# tweakfuzz.net
KiCad netlist of a schematic drawn in EAGLE
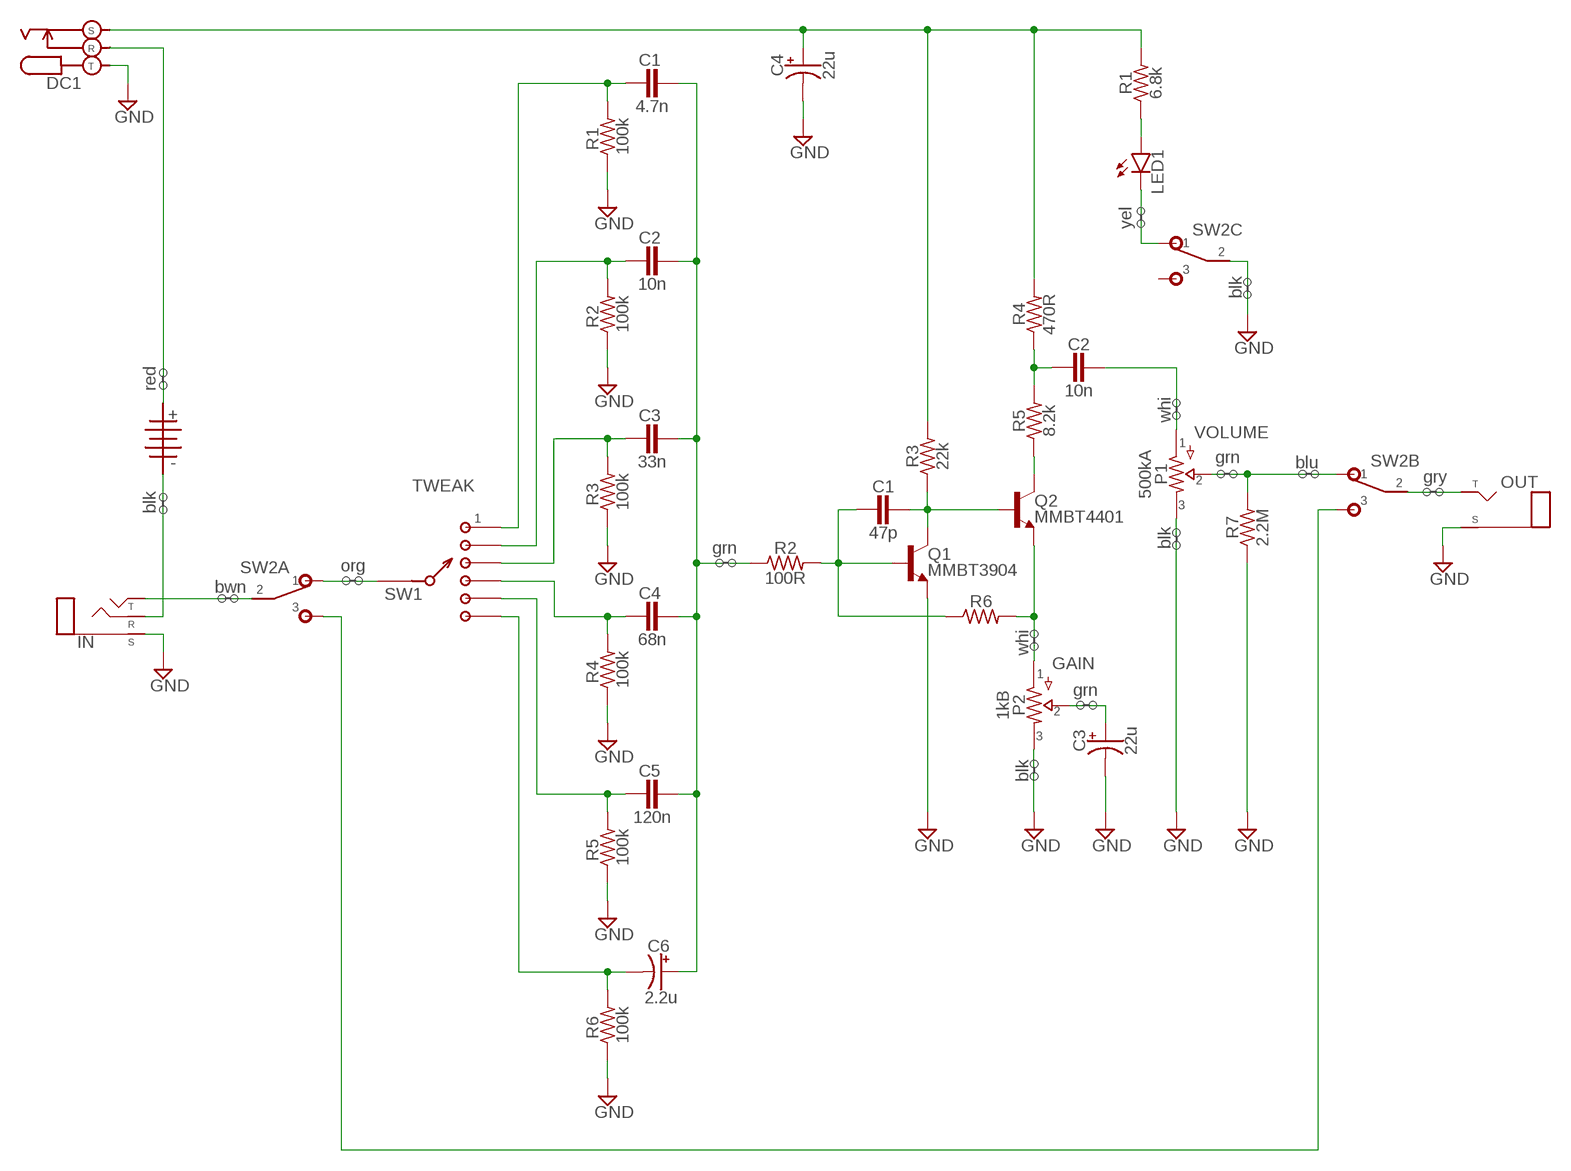
[diagram p0: schematic, sheet 1]

(export (version "E")
  (design (tool "Eeschema 10.0.6"))
  (components
    (comp (ref "1")
      (value "BATTERY")
      (footprint "eagle-import:TWO_PADS")
      (libsource (lib "eagle-import") (part "BATTERY"))
    )
    (comp (ref "C1")
      (value "47p")
      (footprint "eagle-import:BOX_SMALL")
      (libsource (lib "eagle-import") (part "CER/FILMBOX.1"))
    )
    (comp (ref "C1 ")
      (value "4.7n")
      (footprint "eagle-import:BOX_SMALL")
      (libsource (lib "eagle-import") (part "CER/FILMBOX.1"))
    )
    (comp (ref "C2")
      (value "10n")
      (footprint "eagle-import:BOX_SMALL")
      (libsource (lib "eagle-import") (part "CER/FILMBOX.1"))
    )
    (comp (ref "C2 ")
      (value "10n")
      (footprint "eagle-import:BOX_SMALL")
      (libsource (lib "eagle-import") (part "CER/FILMBOX.1"))
    )
    (comp (ref "C3")
      (value "22u")
      (footprint "eagle-import:050_020")
      (libsource (lib "eagle-import") (part "0500"))
    )
    (comp (ref "C3 ")
      (value "33n")
      (footprint "eagle-import:BOX_SMALL")
      (libsource (lib "eagle-import") (part "CER/FILMBOX.1"))
    )
    (comp (ref "C4")
      (value "22u")
      (footprint "eagle-import:050_020")
      (libsource (lib "eagle-import") (part "0500"))
    )
    (comp (ref "C4 ")
      (value "68n")
      (footprint "eagle-import:BOX_SMALL")
      (libsource (lib "eagle-import") (part "CER/FILMBOX.1"))
    )
    (comp (ref "C5 ")
      (value "120n")
      (footprint "eagle-import:BOX_SMALL")
      (libsource (lib "eagle-import") (part "CER/FILMBOX.1"))
    )
    (comp (ref "C6 ")
      (value "2.2u")
      (footprint "eagle-import:050_020")
      (libsource (lib "eagle-import") (part "0500"))
    )
    (comp (ref "DC1")
      (value "DC_KOBICONN")
      (footprint "eagle-import:DC_KOBICONN")
      (libsource (lib "eagle-import") (part "DC_KOBICONN"))
    )
    (comp (ref "IN")
      (value "STEREO")
      (footprint "eagle-import:STEREO_PCB")
      (libsource (lib "eagle-import") (part "STEREO"))
    )
    (comp (ref "LED1")
      (value "LED")
      (footprint "eagle-import:3MM_D")
      (libsource (lib "eagle-import") (part "LED"))
    )
    (comp (ref "OUT")
      (value "MONO")
      (footprint "eagle-import:TWO_PADS")
      (libsource (lib "eagle-import") (part "MONO"))
    )
    (comp (ref "P1")
      (value "500kA")
      (footprint "eagle-import:16MM")
      (libsource (lib "eagle-import") (part "POTS16MM"))
    )
    (comp (ref "P2")
      (value "1kB")
      (footprint "eagle-import:16MM")
      (libsource (lib "eagle-import") (part "POTS16MM"))
    )
    (comp (ref "Q1")
      (value "MMBT3904")
      (footprint "eagle-import:TO92-")
      (libsource (lib "eagle-import") (part "2N3904"))
    )
    (comp (ref "Q2")
      (value "MMBT4401")
      (footprint "eagle-import:TO92-")
      (libsource (lib "eagle-import") (part "2N3904"))
    )
    (comp (ref "R1")
      (value "6.8k")
      (footprint "eagle-import:R0207_3")
      (libsource (lib "eagle-import") (part "R_.3B"))
    )
    (comp (ref "R1 ")
      (value "100k")
      (footprint "eagle-import:R0207_3")
      (libsource (lib "eagle-import") (part "R_.3B"))
    )
    (comp (ref "R2")
      (value "100R")
      (footprint "eagle-import:R0207_3")
      (libsource (lib "eagle-import") (part "R_.3B"))
    )
    (comp (ref "R2 ")
      (value "100k")
      (footprint "eagle-import:R0207_3")
      (libsource (lib "eagle-import") (part "R_.3B"))
    )
    (comp (ref "R3")
      (value "22k")
      (footprint "eagle-import:R0207_3")
      (libsource (lib "eagle-import") (part "R_.3B"))
    )
    (comp (ref "R3 ")
      (value "100k")
      (footprint "eagle-import:R0207_3")
      (libsource (lib "eagle-import") (part "R_.3B"))
    )
    (comp (ref "R4")
      (value "470R")
      (footprint "eagle-import:R0207_3")
      (libsource (lib "eagle-import") (part "R_.3B"))
    )
    (comp (ref "R4 ")
      (value "100k")
      (footprint "eagle-import:R0207_3")
      (libsource (lib "eagle-import") (part "R_.3B"))
    )
    (comp (ref "R5")
      (value "8.2k")
      (footprint "eagle-import:R0207_3")
      (libsource (lib "eagle-import") (part "R_.3B"))
    )
    (comp (ref "R5 ")
      (value "100k")
      (footprint "eagle-import:R0207_3")
      (libsource (lib "eagle-import") (part "R_.3B"))
    )
    (comp (ref "R6")
      (value "R_.3B")
      (footprint "eagle-import:R0207_3")
      (libsource (lib "eagle-import") (part "R_.3B"))
    )
    (comp (ref "R6 ")
      (value "100k")
      (footprint "eagle-import:R0207_3")
      (libsource (lib "eagle-import") (part "R_.3B"))
    )
    (comp (ref "R7")
      (value "2.2M")
      (footprint "eagle-import:R0207_3")
      (libsource (lib "eagle-import") (part "R_.3B"))
    )
    (comp (ref "SW1")
      (value "1P6T")
      (footprint "eagle-import:1P6T")
      (libsource (lib "eagle-import") (part "1P6T"))
    )
    (comp (ref "SW2")
      (value "3PDT")
      (footprint "eagle-import:3PDT")
      (libsource (lib "eagle-import") (part "3PDT"))
    )
  )
  (nets
    (net (code "1") (name "GND") (class "Default")
      (node (ref "C3") (pin "-") (pinfunction "-_-") (pintype "passive"))
      (node (ref "C4") (pin "-") (pinfunction "-_-") (pintype "passive"))
      (node (ref "DC1") (pin "T") (pinfunction "T_T") (pintype "bidirectional"))
      (node (ref "IN") (pin "P$1") (pinfunction "S_P$1") (pintype "passive"))
      (node (ref "OUT") (pin "S") (pinfunction "SLEEVE_S") (pintype "passive"))
      (node (ref "P1") (pin "3") (pinfunction "3_3") (pintype "passive"))
      (node (ref "P2") (pin "3") (pinfunction "3_3") (pintype "passive"))
      (node (ref "Q1") (pin "3") (pinfunction "E_3") (pintype "passive"))
      (node (ref "R1 ") (pin "1") (pinfunction "1_1") (pintype "passive"))
      (node (ref "R2 ") (pin "1") (pinfunction "1_1") (pintype "passive"))
      (node (ref "R3 ") (pin "1") (pinfunction "1_1") (pintype "passive"))
      (node (ref "R4 ") (pin "1") (pinfunction "1_1") (pintype "passive"))
      (node (ref "R5 ") (pin "1") (pinfunction "1_1") (pintype "passive"))
      (node (ref "R6 ") (pin "1") (pinfunction "1_1") (pintype "passive"))
      (node (ref "R7") (pin "1") (pinfunction "1_1") (pintype "passive"))
      (node (ref "SW2") (pin "C2") (pinfunction "2_C2") (pintype "passive"))
    )
    (net (code "2") (name "Net-(1-P$1)") (class "Default")
      (node (ref "1") (pin "T") (pinfunction "P$1_T") (pintype "bidirectional"))
      (node (ref "DC1") (pin "R") (pinfunction "R_R") (pintype "bidirectional"))
    )
    (net (code "3") (name "Net-(1-P$2)") (class "Default")
      (node (ref "1") (pin "S") (pinfunction "P$2_S") (pintype "bidirectional"))
      (node (ref "IN") (pin "P$2") (pinfunction "R_P$2") (pintype "passive"))
    )
    (net (code "4") (name "Net-(C1 -Pad1)") (class "Default")
      (node (ref "C1 ") (pin "1") (pinfunction "1_1") (pintype "passive"))
      (node (ref "C2 ") (pin "1") (pinfunction "1_1") (pintype "passive"))
      (node (ref "C3 ") (pin "1") (pinfunction "1_1") (pintype "passive"))
      (node (ref "C4 ") (pin "1") (pinfunction "1_1") (pintype "passive"))
      (node (ref "C5 ") (pin "1") (pinfunction "1_1") (pintype "passive"))
      (node (ref "C6 ") (pin "+") (pinfunction "+_+") (pintype "passive"))
      (node (ref "R2") (pin "1") (pinfunction "1_1") (pintype "passive"))
    )
    (net (code "5") (name "Net-(C2-Pad1)") (class "Default")
      (node (ref "C2") (pin "1") (pinfunction "1_1") (pintype "passive"))
      (node (ref "P1") (pin "1") (pinfunction "1_1") (pintype "passive"))
    )
    (net (code "6") (name "Net-(C2-Pad2)") (class "Default")
      (node (ref "C2") (pin "2") (pinfunction "2_2") (pintype "passive"))
      (node (ref "R4") (pin "1") (pinfunction "1_1") (pintype "passive"))
      (node (ref "R5") (pin "2") (pinfunction "2_2") (pintype "passive"))
    )
    (net (code "7") (name "Net-(C3-Pad+)") (class "Default")
      (node (ref "C3") (pin "+") (pinfunction "+_+") (pintype "passive"))
      (node (ref "P2") (pin "2") (pinfunction "2_2") (pintype "passive"))
    )
    (net (code "8") (name "Net-(C4-Pad+)") (class "Default")
      (node (ref "C4") (pin "+") (pinfunction "+_+") (pintype "passive"))
      (node (ref "DC1") (pin "S") (pinfunction "S_S") (pintype "bidirectional"))
      (node (ref "R1") (pin "2") (pinfunction "2_2") (pintype "passive"))
      (node (ref "R3") (pin "2") (pinfunction "2_2") (pintype "passive"))
      (node (ref "R4") (pin "2") (pinfunction "2_2") (pintype "passive"))
    )
    (net (code "9") (name "Net-(IN-T)") (class "Default")
      (node (ref "IN") (pin "P$3") (pinfunction "T_P$3") (pintype "passive"))
      (node (ref "SW2") (pin "A2") (pinfunction "2_A2") (pintype "passive"))
    )
    (net (code "10") (name "Net-(LED1-A)") (class "Default")
      (node (ref "LED1") (pin "ANODE") (pinfunction "A_ANODE") (pintype "passive"))
      (node (ref "R1") (pin "1") (pinfunction "1_1") (pintype "passive"))
    )
    (net (code "11") (name "Net-(LED1-C)") (class "Default")
      (node (ref "LED1") (pin "P$1") (pinfunction "C_P$1") (pintype "passive"))
      (node (ref "SW2") (pin "C1") (pinfunction "1_C1") (pintype "passive"))
    )
    (net (code "12") (name "Net-(OUT-TIP)") (class "Default")
      (node (ref "OUT") (pin "T") (pinfunction "TIP_T") (pintype "passive"))
      (node (ref "SW2") (pin "B2") (pinfunction "2_B2") (pintype "passive"))
    )
    (net (code "13") (name "Net-(Q1-B)") (class "Default")
      (node (ref "C1") (pin "2") (pinfunction "2_2") (pintype "passive"))
      (node (ref "Q1") (pin "2") (pinfunction "B_2") (pintype "passive"))
      (node (ref "R2") (pin "2") (pinfunction "2_2") (pintype "passive"))
      (node (ref "R6") (pin "1") (pinfunction "1_1") (pintype "passive"))
    )
    (net (code "14") (name "Net-(Q1-C)") (class "Default")
      (node (ref "C1") (pin "1") (pinfunction "1_1") (pintype "passive"))
      (node (ref "Q1") (pin "1") (pinfunction "C_1") (pintype "passive"))
      (node (ref "Q2") (pin "2") (pinfunction "B_2") (pintype "passive"))
      (node (ref "R3") (pin "1") (pinfunction "1_1") (pintype "passive"))
    )
    (net (code "15") (name "Net-(Q2-C)") (class "Default")
      (node (ref "Q2") (pin "1") (pinfunction "C_1") (pintype "passive"))
      (node (ref "R5") (pin "1") (pinfunction "1_1") (pintype "passive"))
    )
    (net (code "16") (name "Net-(Q2-E)") (class "Default")
      (node (ref "P2") (pin "1") (pinfunction "1_1") (pintype "passive"))
      (node (ref "Q2") (pin "3") (pinfunction "E_3") (pintype "passive"))
      (node (ref "R6") (pin "2") (pinfunction "2_2") (pintype "passive"))
    )
    (net (code "17") (name "Net-(SW1-2)") (class "Default")
      (node (ref "C1 ") (pin "2") (pinfunction "2_2") (pintype "passive"))
      (node (ref "R1 ") (pin "2") (pinfunction "2_2") (pintype "passive"))
      (node (ref "SW1") (pin "1") (pinfunction "2_1") (pintype "bidirectional"))
    )
    (net (code "18") (name "Net-(SW1-3)") (class "Default")
      (node (ref "C2 ") (pin "2") (pinfunction "2_2") (pintype "passive"))
      (node (ref "R2 ") (pin "2") (pinfunction "2_2") (pintype "passive"))
      (node (ref "SW1") (pin "2") (pinfunction "3_2") (pintype "bidirectional"))
    )
    (net (code "19") (name "Net-(SW1-4)") (class "Default")
      (node (ref "C3 ") (pin "2") (pinfunction "2_2") (pintype "passive"))
      (node (ref "R3 ") (pin "2") (pinfunction "2_2") (pintype "passive"))
      (node (ref "SW1") (pin "3") (pinfunction "4_3") (pintype "bidirectional"))
    )
    (net (code "20") (name "Net-(SW1-5)") (class "Default")
      (node (ref "C4 ") (pin "2") (pinfunction "2_2") (pintype "passive"))
      (node (ref "R4 ") (pin "2") (pinfunction "2_2") (pintype "passive"))
      (node (ref "SW1") (pin "4") (pinfunction "5_4") (pintype "bidirectional"))
    )
    (net (code "21") (name "Net-(SW1-6)") (class "Default")
      (node (ref "C5 ") (pin "2") (pinfunction "2_2") (pintype "passive"))
      (node (ref "R5 ") (pin "2") (pinfunction "2_2") (pintype "passive"))
      (node (ref "SW1") (pin "5") (pinfunction "6_5") (pintype "bidirectional"))
    )
    (net (code "22") (name "Net-(SW1-7)") (class "Default")
      (node (ref "C6 ") (pin "-") (pinfunction "-_-") (pintype "passive"))
      (node (ref "R6 ") (pin "2") (pinfunction "2_2") (pintype "passive"))
      (node (ref "SW1") (pin "6") (pinfunction "7_6") (pintype "bidirectional"))
    )
    (net (code "23") (name "Net-(SW1-A)") (class "Default")
      (node (ref "SW1") (pin "7") (pinfunction "A_7") (pintype "bidirectional"))
      (node (ref "SW2") (pin "A1") (pinfunction "1_A1") (pintype "passive"))
    )
    (net (code "24") (name "Net-(SW2A-3)") (class "Default")
      (node (ref "SW2") (pin "A3") (pinfunction "3_A3") (pintype "passive"))
      (node (ref "SW2") (pin "B3") (pinfunction "3_B3") (pintype "passive"))
    )
    (net (code "25") (name "Net-(SW2B-1)") (class "Default")
      (node (ref "P1") (pin "2") (pinfunction "2_2") (pintype "passive"))
      (node (ref "R7") (pin "2") (pinfunction "2_2") (pintype "passive"))
      (node (ref "SW2") (pin "B1") (pinfunction "1_B1") (pintype "passive"))
    )
    (net (code "26") (name "unconnected-(SW2C-3-PadC3)") (class "Default")
      (node (ref "SW2") (pin "C3") (pinfunction "3_C3") (pintype "passive"))
    )
  )
)
